# dcdc-switch.net
KiCad netlist of a schematic drawn in Altium Designer
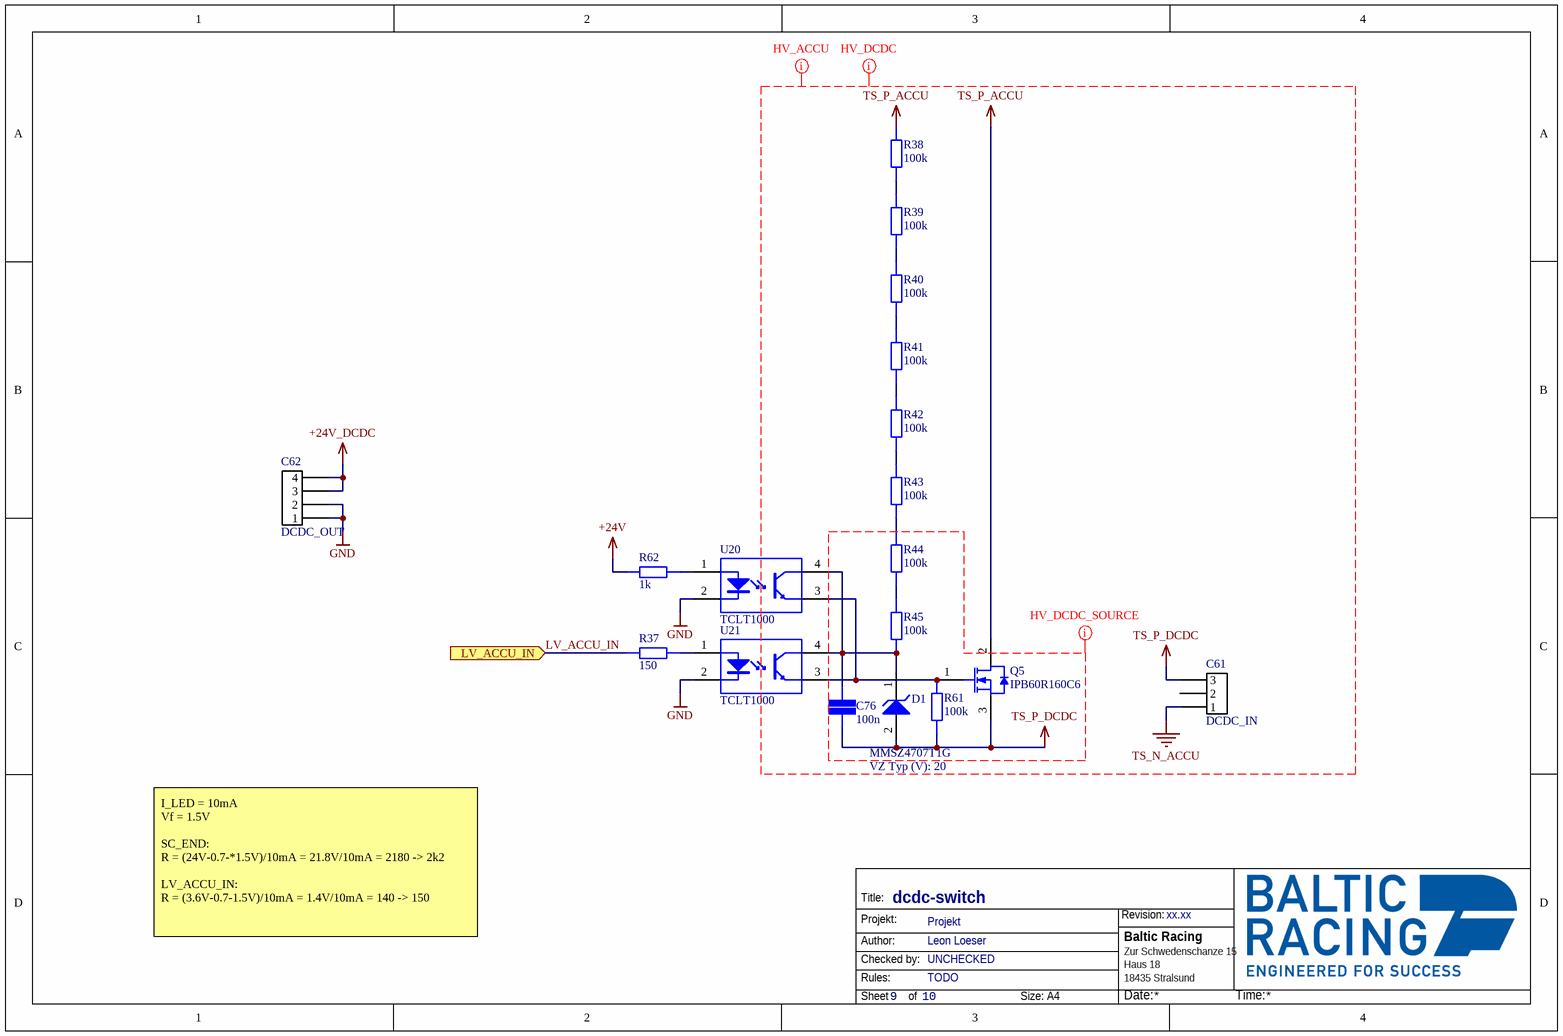
[diagram p0: dcdc-switch.SchDoc]

(export (version "E")
  (design (tool "Eeschema 10.0.6"))
  (components
    (comp (ref "C61")
      (value "DCDC_IN")
      (footprint "43650-0315")
      (description "Molex MicroFit3.0 3-Pin")
      (libsource (lib "Standardbauteile") (part "MicroFit3.0 3-Pin"))
    )
    (comp (ref "C62")
      (value "DCDC_OUT")
      (footprint "76825-0004")
      (description "Molex Mega-Fit 4-Pin\r\n600V\r\n23A")
      (libsource (lib "Standardbauteile") (part "MegaFit 4-Pin"))
    )
    (comp (ref "C76")
      (value "100n")
      (footprint "CAP 0603/1608")
      (description "Capacitor with multiple Footprints")
      (fields (field (name "Comment") "SMD Capacitor"))
      (libsource (lib "Standardbauteile") (part "SMD Capacitor"))
    )
    (comp (ref "D1")
      (value "MMSZ4707T1G")
      (footprint "ONSC-SOD-123-2-425-04_V")
      (description "Zener Voltage Regulator, 500 mW, 2-Pin SOD-123, Pb-Free, Tape and Reel")
      (fields (field (name "MANUFACTURER") "On Semiconductor") (field (name "VZ TYP (V)") "20"))
      (libsource (lib "Altium Content Vault") (part "ONSC-K1A2-2"))
    )
    (comp (ref "Q5")
      (value "IPB60R160C6")
      (footprint "INF-PG-TO263-3-2_N")
      (fields (field (name "MANUFACTURER") "Infineon"))
      (libsource (lib "Altium Content Vault") (part "INF-NEMOS-GDS-3"))
    )
    (comp (ref "R37")
      (value "150")
      (footprint "STACKPOLE CSR1206")
      (description "Resistor with multiple footprints")
      (fields (field (name "Comment") "SMD Resistor"))
      (libsource (lib "Standardbauteile") (part "SMD Resistor"))
    )
    (comp (ref "R38")
      (value "100k")
      (footprint "STACKPOLE CSR1206")
      (description "Resistor with multiple footprints")
      (fields (field (name "Comment") "SMD Resistor"))
      (libsource (lib "Standardbauteile") (part "SMD Resistor"))
    )
    (comp (ref "R39")
      (value "100k")
      (footprint "STACKPOLE CSR1206")
      (description "Resistor with multiple footprints")
      (fields (field (name "Comment") "SMD Resistor"))
      (libsource (lib "Standardbauteile") (part "SMD Resistor"))
    )
    (comp (ref "R40")
      (value "100k")
      (footprint "STACKPOLE CSR1206")
      (description "Resistor with multiple footprints")
      (fields (field (name "Comment") "SMD Resistor"))
      (libsource (lib "Standardbauteile") (part "SMD Resistor"))
    )
    (comp (ref "R41")
      (value "100k")
      (footprint "STACKPOLE CSR1206")
      (description "Resistor with multiple footprints")
      (fields (field (name "Comment") "SMD Resistor"))
      (libsource (lib "Standardbauteile") (part "SMD Resistor"))
    )
    (comp (ref "R42")
      (value "100k")
      (footprint "STACKPOLE CSR1206")
      (description "Resistor with multiple footprints")
      (fields (field (name "Comment") "SMD Resistor"))
      (libsource (lib "Standardbauteile") (part "SMD Resistor"))
    )
    (comp (ref "R43")
      (value "100k")
      (footprint "STACKPOLE CSR1206")
      (description "Resistor with multiple footprints")
      (fields (field (name "Comment") "SMD Resistor"))
      (libsource (lib "Standardbauteile") (part "SMD Resistor"))
    )
    (comp (ref "R44")
      (value "100k")
      (footprint "STACKPOLE CSR1206")
      (description "Resistor with multiple footprints")
      (fields (field (name "Comment") "SMD Resistor"))
      (libsource (lib "Standardbauteile") (part "SMD Resistor"))
    )
    (comp (ref "R45")
      (value "100k")
      (footprint "STACKPOLE CSR1206")
      (description "Resistor with multiple footprints")
      (fields (field (name "Comment") "SMD Resistor"))
      (libsource (lib "Standardbauteile") (part "SMD Resistor"))
    )
    (comp (ref "R61")
      (value "100k")
      (footprint "STACKPOLE CSR0603")
      (description "Resistor with multiple footprints")
      (fields (field (name "Comment") "SMD Resistor"))
      (libsource (lib "Standardbauteile") (part "SMD Resistor"))
    )
    (comp (ref "R62")
      (value "1k")
      (footprint "STACKPOLE CSR1206")
      (description "Resistor with multiple footprints")
      (fields (field (name "Comment") "SMD Resistor"))
      (libsource (lib "Standardbauteile") (part "SMD Resistor"))
    )
    (comp (ref "U20")
      (value "TCLT1000")
      (footprint "VISH-SOP4L-4_V")
      (fields (field (name "MANUFACTURER") "Vishay/Semiconductor"))
      (libsource (lib "Altium Content Vault") (part "OPTO-ACEC-4"))
    )
    (comp (ref "U21")
      (value "TCLT1000")
      (footprint "VISH-SOP4L-4_V")
      (fields (field (name "MANUFACTURER") "Vishay/Semiconductor"))
      (libsource (lib "Altium Content Vault") (part "OPTO-ACEC-4"))
    )
  )
  (nets
    (net (code "1") (name "+24V") (class "Default")
      (node (ref "R62") (pin "1") (pinfunction "1_1") (pintype "passive"))
    )
    (net (code "2") (name "+24V_DCDC") (class "Default")
      (node (ref "C62") (pin "3") (pinfunction "3_3") (pintype "passive"))
      (node (ref "C62") (pin "4") (pinfunction "4_4") (pintype "passive"))
    )
    (net (code "3") (name "/LV_ACCU_IN") (class "Default")
      (node (ref "R37") (pin "1") (pinfunction "1_1") (pintype "passive"))
    )
    (net (code "4") (name "GND") (class "Default")
      (node (ref "C62") (pin "1") (pinfunction "1_1") (pintype "passive"))
      (node (ref "C62") (pin "2") (pinfunction "2_2") (pintype "passive"))
      (node (ref "U20") (pin "2") (pinfunction "C_2") (pintype "passive"))
      (node (ref "U21") (pin "2") (pinfunction "C_2") (pintype "passive"))
    )
    (net (code "5") (name "Net-(D1-K)") (class "Default")
      (node (ref "C76") (pin "2") (pinfunction "2_2") (pintype "passive"))
      (node (ref "D1") (pin "1") (pinfunction "K_1") (pintype "passive"))
      (node (ref "R45") (pin "1") (pinfunction "1_1") (pintype "passive"))
      (node (ref "U20") (pin "4") (pinfunction "C_4") (pintype "passive"))
      (node (ref "U21") (pin "4") (pinfunction "C_4") (pintype "passive"))
    )
    (net (code "6") (name "Net-(Q5-GATE)") (class "Default")
      (node (ref "Q5") (pin "1") (pinfunction "GATE_1") (pintype "passive"))
      (node (ref "R61") (pin "2") (pinfunction "2_2") (pintype "passive"))
      (node (ref "U20") (pin "3") (pinfunction "E_3") (pintype "passive"))
      (node (ref "U21") (pin "3") (pinfunction "E_3") (pintype "passive"))
    )
    (net (code "7") (name "Net-(R38-Pad1)") (class "Default")
      (node (ref "R38") (pin "1") (pinfunction "1_1") (pintype "passive"))
      (node (ref "R39") (pin "2") (pinfunction "2_2") (pintype "passive"))
    )
    (net (code "8") (name "Net-(R39-Pad1)") (class "Default")
      (node (ref "R39") (pin "1") (pinfunction "1_1") (pintype "passive"))
      (node (ref "R40") (pin "2") (pinfunction "2_2") (pintype "passive"))
    )
    (net (code "9") (name "Net-(R40-Pad1)") (class "Default")
      (node (ref "R40") (pin "1") (pinfunction "1_1") (pintype "passive"))
      (node (ref "R41") (pin "2") (pinfunction "2_2") (pintype "passive"))
    )
    (net (code "10") (name "Net-(R41-Pad1)") (class "Default")
      (node (ref "R41") (pin "1") (pinfunction "1_1") (pintype "passive"))
      (node (ref "R42") (pin "2") (pinfunction "2_2") (pintype "passive"))
    )
    (net (code "11") (name "Net-(R42-Pad1)") (class "Default")
      (node (ref "R42") (pin "1") (pinfunction "1_1") (pintype "passive"))
      (node (ref "R43") (pin "2") (pinfunction "2_2") (pintype "passive"))
    )
    (net (code "12") (name "Net-(R43-Pad1)") (class "Default")
      (node (ref "R43") (pin "1") (pinfunction "1_1") (pintype "passive"))
      (node (ref "R44") (pin "2") (pinfunction "2_2") (pintype "passive"))
    )
    (net (code "13") (name "Net-(R44-Pad1)") (class "Default")
      (node (ref "R44") (pin "1") (pinfunction "1_1") (pintype "passive"))
      (node (ref "R45") (pin "2") (pinfunction "2_2") (pintype "passive"))
    )
    (net (code "14") (name "Net-(U20-A)") (class "Default")
      (node (ref "R62") (pin "2") (pinfunction "2_2") (pintype "passive"))
      (node (ref "U20") (pin "1") (pinfunction "A_1") (pintype "passive"))
    )
    (net (code "15") (name "Net-(U21-A)") (class "Default")
      (node (ref "R37") (pin "2") (pinfunction "2_2") (pintype "passive"))
      (node (ref "U21") (pin "1") (pinfunction "A_1") (pintype "passive"))
    )
    (net (code "16") (name "TS_N_ACCU") (class "Default")
      (node (ref "C61") (pin "1") (pinfunction "1_1") (pintype "passive"))
    )
    (net (code "17") (name "TS_P_ACCU") (class "Default")
      (node (ref "Q5") (pin "2") (pinfunction "DRAIN_2") (pintype "passive"))
      (node (ref "R38") (pin "2") (pinfunction "2_2") (pintype "passive"))
    )
    (net (code "18") (name "TS_P_DCDC") (class "Default")
      (node (ref "C61") (pin "3") (pinfunction "3_3") (pintype "passive"))
      (node (ref "C76") (pin "1") (pinfunction "1_1") (pintype "passive"))
      (node (ref "D1") (pin "2") (pinfunction "A_2") (pintype "passive"))
      (node (ref "Q5") (pin "3") (pinfunction "SOURCE_3") (pintype "passive"))
      (node (ref "R61") (pin "1") (pinfunction "1_1") (pintype "passive"))
    )
    (net (code "19") (name "unconnected-(C61-Pad2)") (class "Default")
      (node (ref "C61") (pin "2") (pinfunction "2_2") (pintype "passive"))
    )
  )
)
